# flipflop-sr.net
KiCad netlist of a schematic drawn in EAGLE
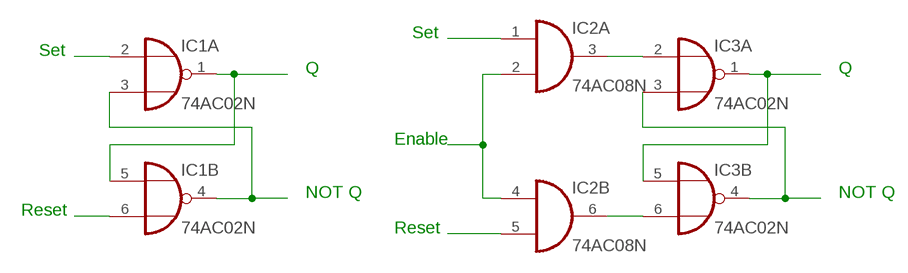
[diagram p0: schematic, sheet 1]

(export (version "E")
  (design (tool "Eeschema 10.0.6"))
  (components
    (comp (ref "IC1")
      (value "74AC02N")
      (footprint "eagle-import:DIL14")
      (libsource (lib "eagle-import") (part "7402NAC"))
    )
    (comp (ref "IC2")
      (value "74AC08N")
      (footprint "eagle-import:DIL14")
      (libsource (lib "eagle-import") (part "7408NAC"))
    )
    (comp (ref "IC3")
      (value "74AC02N")
      (footprint "eagle-import:DIL14")
      (libsource (lib "eagle-import") (part "7402NAC"))
    )
  )
  (nets
    (net (code "1") (name "Net-(IC1A-I1)") (class "Default")
      (node (ref "IC1") (pin "3") (pinfunction "I1_3") (pintype "input"))
      (node (ref "IC1") (pin "4") (pinfunction "O_4") (pintype "output"))
    )
    (net (code "2") (name "Net-(IC1A-O)") (class "Default")
      (node (ref "IC1") (pin "1") (pinfunction "O_1") (pintype "output"))
      (node (ref "IC1") (pin "5") (pinfunction "I0_5") (pintype "input"))
    )
    (net (code "3") (name "Net-(IC2A-I1)") (class "Default")
      (node (ref "IC2") (pin "2") (pinfunction "I1_2") (pintype "input"))
      (node (ref "IC2") (pin "4") (pinfunction "I0_4") (pintype "input"))
    )
    (net (code "4") (name "Net-(IC2A-O)") (class "Default")
      (node (ref "IC2") (pin "3") (pinfunction "O_3") (pintype "output"))
      (node (ref "IC3") (pin "2") (pinfunction "I0_2") (pintype "input"))
    )
    (net (code "5") (name "Net-(IC2B-O)") (class "Default")
      (node (ref "IC2") (pin "6") (pinfunction "O_6") (pintype "output"))
      (node (ref "IC3") (pin "6") (pinfunction "I1_6") (pintype "input"))
    )
    (net (code "6") (name "Net-(IC3A-I1)") (class "Default")
      (node (ref "IC3") (pin "3") (pinfunction "I1_3") (pintype "input"))
      (node (ref "IC3") (pin "4") (pinfunction "O_4") (pintype "output"))
    )
    (net (code "7") (name "Net-(IC3A-O)") (class "Default")
      (node (ref "IC3") (pin "1") (pinfunction "O_1") (pintype "output"))
      (node (ref "IC3") (pin "5") (pinfunction "I0_5") (pintype "input"))
    )
    (net (code "8") (name "unconnected-(IC1A-I0-Pad2)") (class "Default")
      (node (ref "IC1") (pin "2") (pinfunction "I0_2") (pintype "input"))
    )
    (net (code "9") (name "unconnected-(IC1B-I1-Pad6)") (class "Default")
      (node (ref "IC1") (pin "6") (pinfunction "I1_6") (pintype "input"))
    )
    (net (code "10") (name "unconnected-(IC2A-I0-Pad1)") (class "Default")
      (node (ref "IC2") (pin "1") (pinfunction "I0_1") (pintype "input"))
    )
    (net (code "11") (name "unconnected-(IC2B-I1-Pad5)") (class "Default")
      (node (ref "IC2") (pin "5") (pinfunction "I1_5") (pintype "input"))
    )
  )
)
